# CPLD.net
KiCad netlist of a schematic drawn in Altium Designer
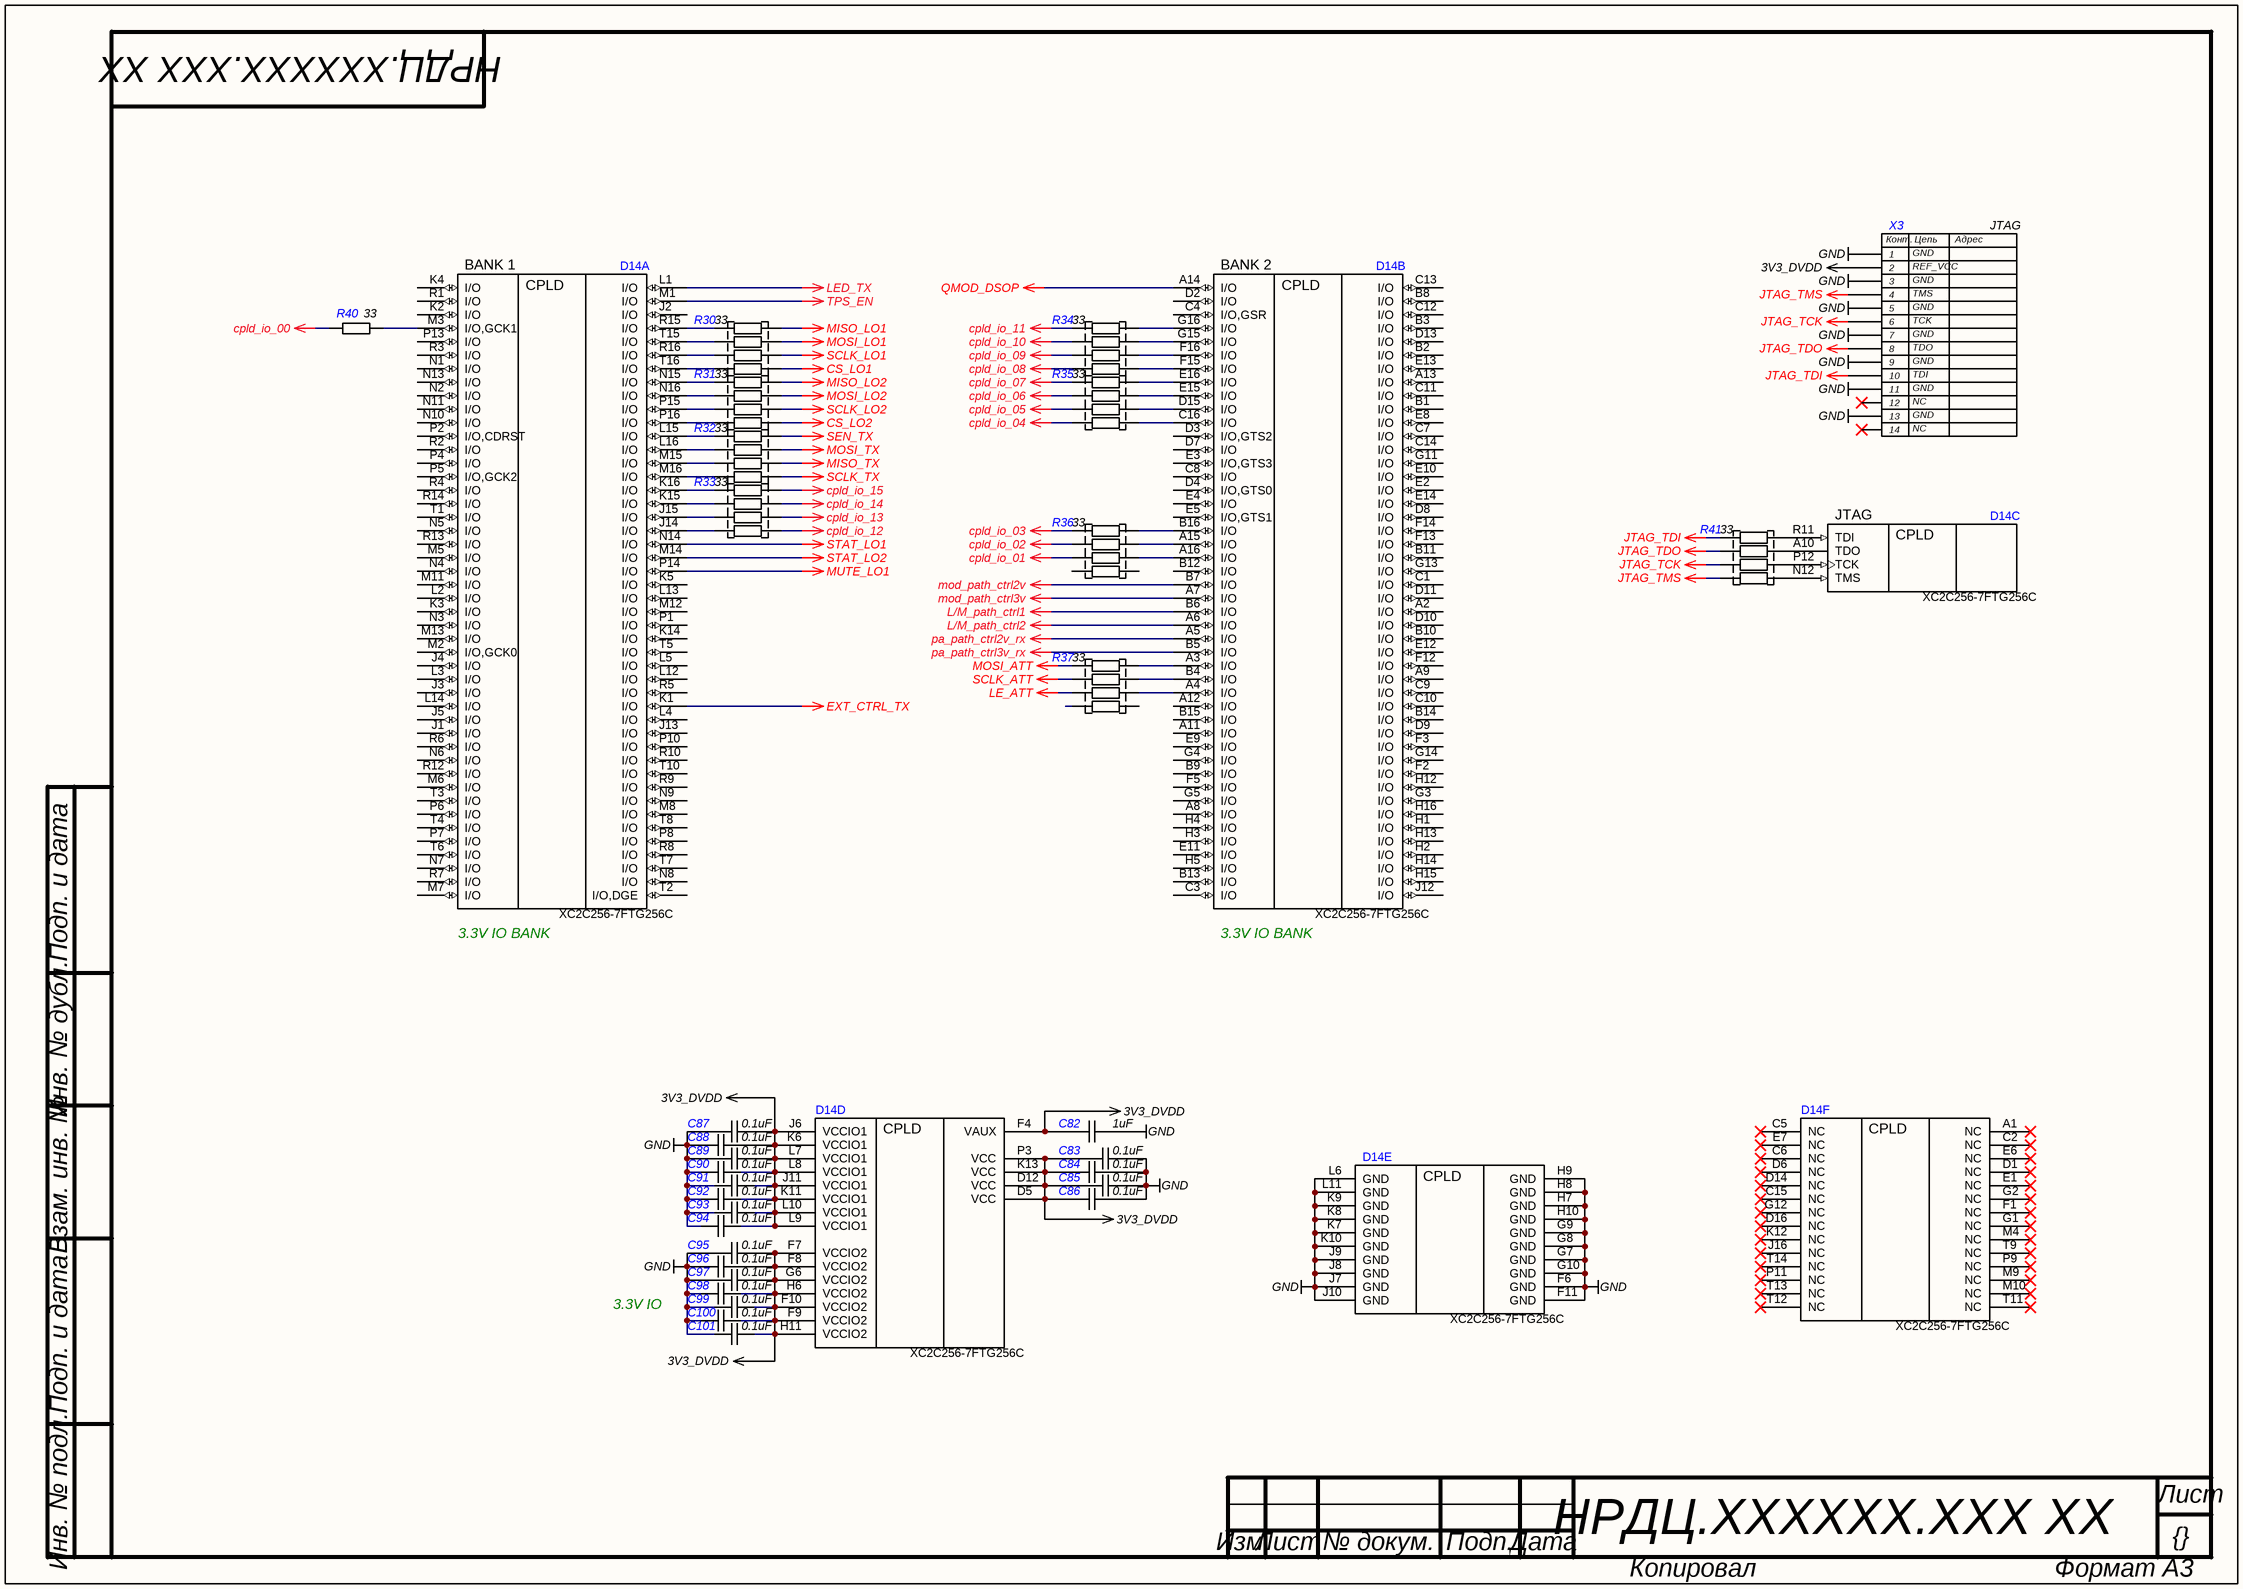
[diagram p0: CPLD.SchDoc]

(export (version "E")
  (design (tool "Eeschema 10.0.6"))
  (components
    (comp (ref "C82")
      (value "1uF")
      (footprint "C0402")
      (description "SMD Capacitor")
      (fields (field (name "MANUFACTURER") "Murata") (field (name "TOLERANCE") "10%"))
      (libsource (lib "Kintex_SDR") (part "CAP"))
    )
    (comp (ref "C83")
      (value "0.1uF")
      (footprint "C0402")
      (description "SMD Capacitor")
      (fields (field (name "MANUFACTURER") "Murata") (field (name "TOLERANCE") "10%"))
      (libsource (lib "Kintex_SDR") (part "CAP"))
    )
    (comp (ref "C84")
      (value "0.1uF")
      (footprint "C0402")
      (description "SMD Capacitor")
      (fields (field (name "MANUFACTURER") "Murata") (field (name "TOLERANCE") "10%"))
      (libsource (lib "Kintex_SDR") (part "CAP"))
    )
    (comp (ref "C85")
      (value "0.1uF")
      (footprint "C0402")
      (description "SMD Capacitor")
      (fields (field (name "MANUFACTURER") "Murata") (field (name "TOLERANCE") "10%"))
      (libsource (lib "Kintex_SDR") (part "CAP"))
    )
    (comp (ref "C86")
      (value "0.1uF")
      (footprint "C0402")
      (description "SMD Capacitor")
      (fields (field (name "MANUFACTURER") "Murata") (field (name "TOLERANCE") "10%"))
      (libsource (lib "Kintex_SDR") (part "CAP"))
    )
    (comp (ref "C87")
      (value "0.1uF")
      (footprint "C0402")
      (description "SMD Capacitor")
      (fields (field (name "MANUFACTURER") "Murata") (field (name "TOLERANCE") "10%"))
      (libsource (lib "Kintex_SDR") (part "CAP"))
    )
    (comp (ref "C88")
      (value "0.1uF")
      (footprint "C0402")
      (description "SMD Capacitor")
      (fields (field (name "MANUFACTURER") "Murata") (field (name "TOLERANCE") "10%"))
      (libsource (lib "Kintex_SDR") (part "CAP"))
    )
    (comp (ref "C89")
      (value "0.1uF")
      (footprint "C0402")
      (description "SMD Capacitor")
      (fields (field (name "MANUFACTURER") "Murata") (field (name "TOLERANCE") "10%"))
      (libsource (lib "Kintex_SDR") (part "CAP"))
    )
    (comp (ref "C90")
      (value "0.1uF")
      (footprint "C0402")
      (description "SMD Capacitor")
      (fields (field (name "MANUFACTURER") "Murata") (field (name "TOLERANCE") "10%"))
      (libsource (lib "Kintex_SDR") (part "CAP"))
    )
    (comp (ref "C91")
      (value "0.1uF")
      (footprint "C0402")
      (description "SMD Capacitor")
      (fields (field (name "MANUFACTURER") "Murata") (field (name "TOLERANCE") "10%"))
      (libsource (lib "Kintex_SDR") (part "CAP"))
    )
    (comp (ref "C92")
      (value "0.1uF")
      (footprint "C0402")
      (description "SMD Capacitor")
      (fields (field (name "MANUFACTURER") "Murata") (field (name "TOLERANCE") "10%"))
      (libsource (lib "Kintex_SDR") (part "CAP"))
    )
    (comp (ref "C93")
      (value "0.1uF")
      (footprint "C0402")
      (description "SMD Capacitor")
      (fields (field (name "MANUFACTURER") "Murata") (field (name "TOLERANCE") "10%"))
      (libsource (lib "Kintex_SDR") (part "CAP"))
    )
    (comp (ref "C94")
      (value "0.1uF")
      (footprint "C0402")
      (description "SMD Capacitor")
      (fields (field (name "MANUFACTURER") "Murata") (field (name "TOLERANCE") "10%"))
      (libsource (lib "Kintex_SDR") (part "CAP"))
    )
    (comp (ref "C95")
      (value "0.1uF")
      (footprint "C0402")
      (description "SMD Capacitor")
      (fields (field (name "MANUFACTURER") "Murata") (field (name "TOLERANCE") "10%"))
      (libsource (lib "Kintex_SDR") (part "CAP"))
    )
    (comp (ref "C96")
      (value "0.1uF")
      (footprint "C0402")
      (description "SMD Capacitor")
      (fields (field (name "MANUFACTURER") "Murata") (field (name "TOLERANCE") "10%"))
      (libsource (lib "Kintex_SDR") (part "CAP"))
    )
    (comp (ref "C97")
      (value "0.1uF")
      (footprint "C0402")
      (description "SMD Capacitor")
      (fields (field (name "MANUFACTURER") "Murata") (field (name "TOLERANCE") "10%"))
      (libsource (lib "Kintex_SDR") (part "CAP"))
    )
    (comp (ref "C98")
      (value "0.1uF")
      (footprint "C0402")
      (description "SMD Capacitor")
      (fields (field (name "MANUFACTURER") "Murata") (field (name "TOLERANCE") "10%"))
      (libsource (lib "Kintex_SDR") (part "CAP"))
    )
    (comp (ref "C99")
      (value "0.1uF")
      (footprint "C0402")
      (description "SMD Capacitor")
      (fields (field (name "MANUFACTURER") "Murata") (field (name "TOLERANCE") "10%"))
      (libsource (lib "Kintex_SDR") (part "CAP"))
    )
    (comp (ref "C100")
      (value "0.1uF")
      (footprint "C0402")
      (description "SMD Capacitor")
      (fields (field (name "MANUFACTURER") "Murata") (field (name "TOLERANCE") "10%"))
      (libsource (lib "Kintex_SDR") (part "CAP"))
    )
    (comp (ref "C101")
      (value "0.1uF")
      (footprint "C0402")
      (description "SMD Capacitor")
      (fields (field (name "MANUFACTURER") "Murata") (field (name "TOLERANCE") "10%"))
      (libsource (lib "Kintex_SDR") (part "CAP"))
    )
    (comp (ref "D14")
      (value "XC2C256-7FTG256C")
      (footprint "DBLib:FTG256")
      (description "CoolRunner-II 1.8V, 256 Macrocell CPLD, 184 User I/Os, 256-Ball FTBGA, Commercial Grade, Pb-Free")
      (libsource (lib "DBLib") (part "XC2C256-7FTG256C"))
    )
    (comp (ref "R30")
      (value "33")
      (footprint "EXN8V")
      (description "Chip Resistor Array")
      (fields (field (name "TOLERANCE") "5%") (field (name "MANUFACTURER") "Panasonic"))
      (libsource (lib "") (part "RES 4x0402_1"))
    )
    (comp (ref "R31")
      (value "33")
      (footprint "EXN8V")
      (description "Chip Resistor Array")
      (fields (field (name "TOLERANCE") "5%") (field (name "MANUFACTURER") "Panasonic"))
      (libsource (lib "") (part "RES 4x0402_2"))
    )
    (comp (ref "R32")
      (value "33")
      (footprint "EXN8V")
      (description "Chip Resistor Array")
      (fields (field (name "TOLERANCE") "5%") (field (name "MANUFACTURER") "Panasonic"))
      (libsource (lib "") (part "RES 4x0402_2"))
    )
    (comp (ref "R33")
      (value "33")
      (footprint "EXN8V")
      (description "Chip Resistor Array")
      (fields (field (name "TOLERANCE") "5%") (field (name "MANUFACTURER") "Panasonic"))
      (libsource (lib "Kintex_SDR") (part "RES 4x0402"))
    )
    (comp (ref "R34")
      (value "33")
      (footprint "EXN8V")
      (description "Chip Resistor Array")
      (fields (field (name "TOLERANCE") "5%") (field (name "MANUFACTURER") "Panasonic"))
      (libsource (lib "") (part "RES 4x0402_3"))
    )
    (comp (ref "R35")
      (value "33")
      (footprint "EXN8V")
      (description "Chip Resistor Array")
      (fields (field (name "TOLERANCE") "5%") (field (name "MANUFACTURER") "Panasonic"))
      (libsource (lib "") (part "RES 4x0402_3"))
    )
    (comp (ref "R36")
      (value "33")
      (footprint "EXN8V")
      (description "Chip Resistor Array")
      (fields (field (name "TOLERANCE") "5%") (field (name "MANUFACTURER") "Panasonic"))
      (libsource (lib "") (part "RES 4x0402_3"))
    )
    (comp (ref "R37")
      (value "33")
      (footprint "EXN8V")
      (description "Chip Resistor Array")
      (fields (field (name "TOLERANCE") "5%") (field (name "MANUFACTURER") "Panasonic"))
      (libsource (lib "") (part "RES 4x0402_4"))
    )
    (comp (ref "R40")
      (value "33")
      (footprint "R0402")
      (description "SMD Resistor")
      (fields (field (name "POWER") "0.1 Wt") (field (name "TOLERANCE") "1%"))
      (libsource (lib "Kintex_SDR") (part "RES"))
    )
    (comp (ref "R41")
      (value "33")
      (footprint "EXN8V")
      (description "Chip Resistor Array")
      (fields (field (name "TOLERANCE") "5%") (field (name "MANUFACTURER") "Panasonic"))
      (libsource (lib "") (part "RES 4x0402_4"))
    )
    (comp (ref "X3")
      (value "JTAG")
      (footprint "DBLib:JTAG Mail 2mm")
      (description "2.00mm Pitch, Milli-Grid PCB Header, Dual Row, Vertical, Through Hole, Shrouded, 14\r\nCircuits")
      (fields (field (name "MANUFACTURER") "Molex"))
      (libsource (lib "DBLib") (part "HDR Debug_14-pin"))
    )
  )
  (nets
    (net (code "1") (name "3V3_DVDD") (class "Default")
      (node (ref "C100") (pin "2") (pinfunction "2_2") (pintype "passive"))
      (node (ref "C101") (pin "2") (pinfunction "2_2") (pintype "passive"))
      (node (ref "C82") (pin "1") (pinfunction "1_1") (pintype "passive"))
      (node (ref "C83") (pin "1") (pinfunction "1_1") (pintype "passive"))
      (node (ref "C84") (pin "1") (pinfunction "1_1") (pintype "passive"))
      (node (ref "C85") (pin "1") (pinfunction "1_1") (pintype "passive"))
      (node (ref "C86") (pin "1") (pinfunction "1_1") (pintype "passive"))
      (node (ref "C87") (pin "2") (pinfunction "2_2") (pintype "passive"))
      (node (ref "C88") (pin "2") (pinfunction "2_2") (pintype "passive"))
      (node (ref "C89") (pin "2") (pinfunction "2_2") (pintype "passive"))
      (node (ref "C90") (pin "2") (pinfunction "2_2") (pintype "passive"))
      (node (ref "C91") (pin "2") (pinfunction "2_2") (pintype "passive"))
      (node (ref "C92") (pin "2") (pinfunction "2_2") (pintype "passive"))
      (node (ref "C93") (pin "2") (pinfunction "2_2") (pintype "passive"))
      (node (ref "C94") (pin "2") (pinfunction "2_2") (pintype "passive"))
      (node (ref "C95") (pin "2") (pinfunction "2_2") (pintype "passive"))
      (node (ref "C96") (pin "2") (pinfunction "2_2") (pintype "passive"))
      (node (ref "C97") (pin "2") (pinfunction "2_2") (pintype "passive"))
      (node (ref "C98") (pin "2") (pinfunction "2_2") (pintype "passive"))
      (node (ref "C99") (pin "2") (pinfunction "2_2") (pintype "passive"))
      (node (ref "D14") (pin "D12") (pinfunction "VCC_D12") (pintype "power_in"))
      (node (ref "D14") (pin "D5") (pinfunction "VCC_D5") (pintype "power_in"))
      (node (ref "D14") (pin "F10") (pinfunction "VCCIO2_F10") (pintype "power_in"))
      (node (ref "D14") (pin "F4") (pinfunction "VAUX_F4") (pintype "power_in"))
      (node (ref "D14") (pin "F7") (pinfunction "VCCIO2_F7") (pintype "power_in"))
      (node (ref "D14") (pin "F8") (pinfunction "VCCIO2_F8") (pintype "power_in"))
      (node (ref "D14") (pin "F9") (pinfunction "VCCIO2_F9") (pintype "power_in"))
      (node (ref "D14") (pin "G6") (pinfunction "VCCIO2_G6") (pintype "power_in"))
      (node (ref "D14") (pin "H11") (pinfunction "VCCIO2_H11") (pintype "power_in"))
      (node (ref "D14") (pin "H6") (pinfunction "VCCIO2_H6") (pintype "power_in"))
      (node (ref "D14") (pin "J11") (pinfunction "VCCIO1_J11") (pintype "power_in"))
      (node (ref "D14") (pin "J6") (pinfunction "VCCIO1_J6") (pintype "power_in"))
      (node (ref "D14") (pin "K11") (pinfunction "VCCIO1_K11") (pintype "power_in"))
      (node (ref "D14") (pin "K13") (pinfunction "VCC_K13") (pintype "power_in"))
      (node (ref "D14") (pin "K6") (pinfunction "VCCIO1_K6") (pintype "power_in"))
      (node (ref "D14") (pin "L10") (pinfunction "VCCIO1_L10") (pintype "power_in"))
      (node (ref "D14") (pin "L7") (pinfunction "VCCIO1_L7") (pintype "power_in"))
      (node (ref "D14") (pin "L8") (pinfunction "VCCIO1_L8") (pintype "power_in"))
      (node (ref "D14") (pin "L9") (pinfunction "VCCIO1_L9") (pintype "power_in"))
      (node (ref "D14") (pin "P3") (pinfunction "VCC_P3") (pintype "power_in"))
      (node (ref "X3") (pin "2") (pinfunction "2_2") (pintype "passive"))
    )
    (net (code "2") (name "CS_LO1") (class "Default")
      (node (ref "R30") (pin "5") (pinfunction "5_5") (pintype "passive"))
    )
    (net (code "3") (name "CS_LO2") (class "Default")
      (node (ref "R31") (pin "5") (pinfunction "5_5") (pintype "passive"))
    )
    (net (code "4") (name "EXT_CTRL_TX") (class "Default")
      (node (ref "D14") (pin "K1") (pinfunction "I/O_K1") (pintype "bidirectional"))
    )
    (net (code "5") (name "GND") (class "Default")
      (node (ref "C100") (pin "1") (pinfunction "1_1") (pintype "passive"))
      (node (ref "C101") (pin "1") (pinfunction "1_1") (pintype "passive"))
      (node (ref "C82") (pin "2") (pinfunction "2_2") (pintype "passive"))
      (node (ref "C83") (pin "2") (pinfunction "2_2") (pintype "passive"))
      (node (ref "C84") (pin "2") (pinfunction "2_2") (pintype "passive"))
      (node (ref "C85") (pin "2") (pinfunction "2_2") (pintype "passive"))
      (node (ref "C86") (pin "2") (pinfunction "2_2") (pintype "passive"))
      (node (ref "C87") (pin "1") (pinfunction "1_1") (pintype "passive"))
      (node (ref "C88") (pin "1") (pinfunction "1_1") (pintype "passive"))
      (node (ref "C89") (pin "1") (pinfunction "1_1") (pintype "passive"))
      (node (ref "C90") (pin "1") (pinfunction "1_1") (pintype "passive"))
      (node (ref "C91") (pin "1") (pinfunction "1_1") (pintype "passive"))
      (node (ref "C92") (pin "1") (pinfunction "1_1") (pintype "passive"))
      (node (ref "C93") (pin "1") (pinfunction "1_1") (pintype "passive"))
      (node (ref "C94") (pin "1") (pinfunction "1_1") (pintype "passive"))
      (node (ref "C95") (pin "1") (pinfunction "1_1") (pintype "passive"))
      (node (ref "C96") (pin "1") (pinfunction "1_1") (pintype "passive"))
      (node (ref "C97") (pin "1") (pinfunction "1_1") (pintype "passive"))
      (node (ref "C98") (pin "1") (pinfunction "1_1") (pintype "passive"))
      (node (ref "C99") (pin "1") (pinfunction "1_1") (pintype "passive"))
      (node (ref "D14") (pin "F11") (pinfunction "GND_F11") (pintype "power_in"))
      (node (ref "D14") (pin "F6") (pinfunction "GND_F6") (pintype "power_in"))
      (node (ref "D14") (pin "G10") (pinfunction "GND_G10") (pintype "power_in"))
      (node (ref "D14") (pin "G7") (pinfunction "GND_G7") (pintype "power_in"))
      (node (ref "D14") (pin "G8") (pinfunction "GND_G8") (pintype "power_in"))
      (node (ref "D14") (pin "G9") (pinfunction "GND_G9") (pintype "power_in"))
      (node (ref "D14") (pin "H10") (pinfunction "GND_H10") (pintype "power_in"))
      (node (ref "D14") (pin "H7") (pinfunction "GND_H7") (pintype "power_in"))
      (node (ref "D14") (pin "H8") (pinfunction "GND_H8") (pintype "power_in"))
      (node (ref "D14") (pin "H9") (pinfunction "GND_H9") (pintype "power_in"))
      (node (ref "D14") (pin "J10") (pinfunction "GND_J10") (pintype "power_in"))
      (node (ref "D14") (pin "J7") (pinfunction "GND_J7") (pintype "power_in"))
      (node (ref "D14") (pin "J8") (pinfunction "GND_J8") (pintype "power_in"))
      (node (ref "D14") (pin "J9") (pinfunction "GND_J9") (pintype "power_in"))
      (node (ref "D14") (pin "K10") (pinfunction "GND_K10") (pintype "power_in"))
      (node (ref "D14") (pin "K7") (pinfunction "GND_K7") (pintype "power_in"))
      (node (ref "D14") (pin "K8") (pinfunction "GND_K8") (pintype "power_in"))
      (node (ref "D14") (pin "K9") (pinfunction "GND_K9") (pintype "power_in"))
      (node (ref "D14") (pin "L11") (pinfunction "GND_L11") (pintype "power_in"))
      (node (ref "D14") (pin "L6") (pinfunction "GND_L6") (pintype "power_in"))
      (node (ref "X3") (pin "1") (pinfunction "1_1") (pintype "passive"))
      (node (ref "X3") (pin "11") (pinfunction "11_11") (pintype "passive"))
      (node (ref "X3") (pin "13") (pinfunction "13_13") (pintype "passive"))
      (node (ref "X3") (pin "3") (pinfunction "3_3") (pintype "passive"))
      (node (ref "X3") (pin "5") (pinfunction "5_5") (pintype "passive"))
      (node (ref "X3") (pin "7") (pinfunction "7_7") (pintype "passive"))
      (node (ref "X3") (pin "9") (pinfunction "9_9") (pintype "passive"))
    )
    (net (code "6") (name "JTAG_TCK") (class "Default")
      (node (ref "R41") (pin "6") (pinfunction "6_6") (pintype "passive"))
      (node (ref "X3") (pin "6") (pinfunction "6_6") (pintype "passive"))
    )
    (net (code "7") (name "JTAG_TDI") (class "Default")
      (node (ref "R41") (pin "8") (pinfunction "8_8") (pintype "passive"))
      (node (ref "X3") (pin "10") (pinfunction "10_10") (pintype "passive"))
    )
    (net (code "8") (name "JTAG_TDO") (class "Default")
      (node (ref "R41") (pin "7") (pinfunction "7_7") (pintype "passive"))
      (node (ref "X3") (pin "8") (pinfunction "8_8") (pintype "passive"))
    )
    (net (code "9") (name "JTAG_TMS") (class "Default")
      (node (ref "R41") (pin "5") (pinfunction "5_5") (pintype "passive"))
      (node (ref "X3") (pin "4") (pinfunction "4_4") (pintype "passive"))
    )
    (net (code "10") (name "LED_TX") (class "Default")
      (node (ref "D14") (pin "L1") (pinfunction "I/O_L1") (pintype "bidirectional"))
    )
    (net (code "11") (name "LE_ATT") (class "Default")
      (node (ref "R37") (pin "6") (pinfunction "6_6") (pintype "passive"))
    )
    (net (code "12") (name "L{slash}M_path_ctrl1") (class "Default")
      (node (ref "D14") (pin "B6") (pinfunction "I/O_B6") (pintype "bidirectional"))
    )
    (net (code "13") (name "L{slash}M_path_ctrl2") (class "Default")
      (node (ref "D14") (pin "A6") (pinfunction "I/O_A6") (pintype "bidirectional"))
    )
    (net (code "14") (name "MISO_LO1") (class "Default")
      (node (ref "R30") (pin "8") (pinfunction "8_8") (pintype "passive"))
    )
    (net (code "15") (name "MISO_LO2") (class "Default")
      (node (ref "R31") (pin "8") (pinfunction "8_8") (pintype "passive"))
    )
    (net (code "16") (name "MISO_TX") (class "Default")
      (node (ref "R32") (pin "6") (pinfunction "6_6") (pintype "passive"))
    )
    (net (code "17") (name "MOSI_ATT") (class "Default")
      (node (ref "R37") (pin "8") (pinfunction "8_8") (pintype "passive"))
    )
    (net (code "18") (name "MOSI_LO1") (class "Default")
      (node (ref "R30") (pin "7") (pinfunction "7_7") (pintype "passive"))
    )
    (net (code "19") (name "MOSI_LO2") (class "Default")
      (node (ref "R31") (pin "7") (pinfunction "7_7") (pintype "passive"))
    )
    (net (code "20") (name "MOSI_TX") (class "Default")
      (node (ref "R32") (pin "7") (pinfunction "7_7") (pintype "passive"))
    )
    (net (code "21") (name "MUTE_LO1") (class "Default")
      (node (ref "D14") (pin "P14") (pinfunction "I/O_P14") (pintype "bidirectional"))
    )
    (net (code "22") (name "Net-(D14A-I{slash}O,GCK1)") (class "Default")
      (node (ref "D14") (pin "M3") (pinfunction "I/O,GCK1_M3") (pintype "bidirectional"))
      (node (ref "R40") (pin "1") (pinfunction "1_1") (pintype "passive"))
    )
    (net (code "23") (name "Net-(D14A-I{slash}O-PadJ14)") (class "Default")
      (node (ref "D14") (pin "J14") (pinfunction "I/O_J14") (pintype "bidirectional"))
      (node (ref "R33") (pin "1") (pinfunction "1_1") (pintype "passive"))
    )
    (net (code "24") (name "Net-(D14A-I{slash}O-PadJ15)") (class "Default")
      (node (ref "D14") (pin "J15") (pinfunction "I/O_J15") (pintype "bidirectional"))
      (node (ref "R33") (pin "2") (pinfunction "2_2") (pintype "passive"))
    )
    (net (code "25") (name "Net-(D14A-I{slash}O-PadK15)") (class "Default")
      (node (ref "D14") (pin "K15") (pinfunction "I/O_K15") (pintype "bidirectional"))
      (node (ref "R33") (pin "3") (pinfunction "3_3") (pintype "passive"))
    )
    (net (code "26") (name "Net-(D14A-I{slash}O-PadK16)") (class "Default")
      (node (ref "D14") (pin "K16") (pinfunction "I/O_K16") (pintype "bidirectional"))
      (node (ref "R33") (pin "4") (pinfunction "4_4") (pintype "passive"))
    )
    (net (code "27") (name "Net-(D14A-I{slash}O-PadL15)") (class "Default")
      (node (ref "D14") (pin "L15") (pinfunction "I/O_L15") (pintype "bidirectional"))
      (node (ref "R32") (pin "1") (pinfunction "1_1") (pintype "passive"))
    )
    (net (code "28") (name "Net-(D14A-I{slash}O-PadL16)") (class "Default")
      (node (ref "D14") (pin "L16") (pinfunction "I/O_L16") (pintype "bidirectional"))
      (node (ref "R32") (pin "2") (pinfunction "2_2") (pintype "passive"))
    )
    (net (code "29") (name "Net-(D14A-I{slash}O-PadM15)") (class "Default")
      (node (ref "D14") (pin "M15") (pinfunction "I/O_M15") (pintype "bidirectional"))
      (node (ref "R32") (pin "3") (pinfunction "3_3") (pintype "passive"))
    )
    (net (code "30") (name "Net-(D14A-I{slash}O-PadM16)") (class "Default")
      (node (ref "D14") (pin "M16") (pinfunction "I/O_M16") (pintype "bidirectional"))
      (node (ref "R32") (pin "4") (pinfunction "4_4") (pintype "passive"))
    )
    (net (code "31") (name "Net-(D14A-I{slash}O-PadN15)") (class "Default")
      (node (ref "D14") (pin "N15") (pinfunction "I/O_N15") (pintype "bidirectional"))
      (node (ref "R31") (pin "1") (pinfunction "1_1") (pintype "passive"))
    )
    (net (code "32") (name "Net-(D14A-I{slash}O-PadN16)") (class "Default")
      (node (ref "D14") (pin "N16") (pinfunction "I/O_N16") (pintype "bidirectional"))
      (node (ref "R31") (pin "2") (pinfunction "2_2") (pintype "passive"))
    )
    (net (code "33") (name "Net-(D14A-I{slash}O-PadP15)") (class "Default")
      (node (ref "D14") (pin "P15") (pinfunction "I/O_P15") (pintype "bidirectional"))
      (node (ref "R31") (pin "3") (pinfunction "3_3") (pintype "passive"))
    )
    (net (code "34") (name "Net-(D14A-I{slash}O-PadP16)") (class "Default")
      (node (ref "D14") (pin "P16") (pinfunction "I/O_P16") (pintype "bidirectional"))
      (node (ref "R31") (pin "4") (pinfunction "4_4") (pintype "passive"))
    )
    (net (code "35") (name "Net-(D14A-I{slash}O-PadR15)") (class "Default")
      (node (ref "D14") (pin "R15") (pinfunction "I/O_R15") (pintype "bidirectional"))
      (node (ref "R30") (pin "1") (pinfunction "1_1") (pintype "passive"))
    )
    (net (code "36") (name "Net-(D14A-I{slash}O-PadR16)") (class "Default")
      (node (ref "D14") (pin "R16") (pinfunction "I/O_R16") (pintype "bidirectional"))
      (node (ref "R30") (pin "2") (pinfunction "2_2") (pintype "passive"))
    )
    (net (code "37") (name "Net-(D14A-I{slash}O-PadT15)") (class "Default")
      (node (ref "D14") (pin "T15") (pinfunction "I/O_T15") (pintype "bidirectional"))
      (node (ref "R30") (pin "3") (pinfunction "3_3") (pintype "passive"))
    )
    (net (code "38") (name "Net-(D14A-I{slash}O-PadT16)") (class "Default")
      (node (ref "D14") (pin "T16") (pinfunction "I/O_T16") (pintype "bidirectional"))
      (node (ref "R30") (pin "4") (pinfunction "4_4") (pintype "passive"))
    )
    (net (code "39") (name "Net-(D14B-I{slash}O-PadA3)") (class "Default")
      (node (ref "D14") (pin "A3") (pinfunction "I/O_A3") (pintype "bidirectional"))
      (node (ref "R37") (pin "1") (pinfunction "1_1") (pintype "passive"))
    )
    (net (code "40") (name "Net-(D14B-I{slash}O-PadA4)") (class "Default")
      (node (ref "D14") (pin "A4") (pinfunction "I/O_A4") (pintype "bidirectional"))
      (node (ref "R37") (pin "3") (pinfunction "3_3") (pintype "passive"))
    )
    (net (code "41") (name "Net-(D14B-I{slash}O-PadA15)") (class "Default")
      (node (ref "D14") (pin "A15") (pinfunction "I/O_A15") (pintype "bidirectional"))
      (node (ref "R36") (pin "3") (pinfunction "3_3") (pintype "passive"))
    )
    (net (code "42") (name "Net-(D14B-I{slash}O-PadA16)") (class "Default")
      (node (ref "D14") (pin "A16") (pinfunction "I/O_A16") (pintype "bidirectional"))
      (node (ref "R36") (pin "2") (pinfunction "2_2") (pintype "passive"))
    )
    (net (code "43") (name "Net-(D14B-I{slash}O-PadB4)") (class "Default")
      (node (ref "D14") (pin "B4") (pinfunction "I/O_B4") (pintype "bidirectional"))
      (node (ref "R37") (pin "2") (pinfunction "2_2") (pintype "passive"))
    )
    (net (code "44") (name "Net-(D14B-I{slash}O-PadB16)") (class "Default")
      (node (ref "D14") (pin "B16") (pinfunction "I/O_B16") (pintype "bidirectional"))
      (node (ref "R36") (pin "4") (pinfunction "4_4") (pintype "passive"))
    )
    (net (code "45") (name "Net-(D14B-I{slash}O-PadC16)") (class "Default")
      (node (ref "D14") (pin "C16") (pinfunction "I/O_C16") (pintype "bidirectional"))
      (node (ref "R35") (pin "1") (pinfunction "1_1") (pintype "passive"))
    )
    (net (code "46") (name "Net-(D14B-I{slash}O-PadD15)") (class "Default")
      (node (ref "D14") (pin "D15") (pinfunction "I/O_D15") (pintype "bidirectional"))
      (node (ref "R35") (pin "2") (pinfunction "2_2") (pintype "passive"))
    )
    (net (code "47") (name "Net-(D14B-I{slash}O-PadE15)") (class "Default")
      (node (ref "D14") (pin "E15") (pinfunction "I/O_E15") (pintype "bidirectional"))
      (node (ref "R35") (pin "3") (pinfunction "3_3") (pintype "passive"))
    )
    (net (code "48") (name "Net-(D14B-I{slash}O-PadE16)") (class "Default")
      (node (ref "D14") (pin "E16") (pinfunction "I/O_E16") (pintype "bidirectional"))
      (node (ref "R35") (pin "4") (pinfunction "4_4") (pintype "passive"))
    )
    (net (code "49") (name "Net-(D14B-I{slash}O-PadF15)") (class "Default")
      (node (ref "D14") (pin "F15") (pinfunction "I/O_F15") (pintype "bidirectional"))
      (node (ref "R34") (pin "1") (pinfunction "1_1") (pintype "passive"))
    )
    (net (code "50") (name "Net-(D14B-I{slash}O-PadF16)") (class "Default")
      (node (ref "D14") (pin "F16") (pinfunction "I/O_F16") (pintype "bidirectional"))
      (node (ref "R34") (pin "2") (pinfunction "2_2") (pintype "passive"))
    )
    (net (code "51") (name "Net-(D14B-I{slash}O-PadG15)") (class "Default")
      (node (ref "D14") (pin "G15") (pinfunction "I/O_G15") (pintype "bidirectional"))
      (node (ref "R34") (pin "3") (pinfunction "3_3") (pintype "passive"))
    )
    (net (code "52") (name "Net-(D14B-I{slash}O-PadG16)") (class "Default")
      (node (ref "D14") (pin "G16") (pinfunction "I/O_G16") (pintype "bidirectional"))
      (node (ref "R34") (pin "4") (pinfunction "4_4") (pintype "passive"))
    )
    (net (code "53") (name "Net-(D14C-TCK)") (class "Default")
      (node (ref "D14") (pin "P12") (pinfunction "TCK_P12") (pintype "input"))
      (node (ref "R41") (pin "3") (pinfunction "3_3") (pintype "passive"))
    )
    (net (code "54") (name "Net-(D14C-TDI)") (class "Default")
      (node (ref "D14") (pin "R11") (pinfunction "TDI_R11") (pintype "input"))
      (node (ref "R41") (pin "1") (pinfunction "1_1") (pintype "passive"))
    )
    (net (code "55") (name "Net-(D14C-TDO)") (class "Default")
      (node (ref "D14") (pin "A10") (pinfunction "TDO_A10") (pintype "passive"))
      (node (ref "R41") (pin "2") (pinfunction "2_2") (pintype "passive"))
    )
    (net (code "56") (name "Net-(D14C-TMS)") (class "Default")
      (node (ref "D14") (pin "N12") (pinfunction "TMS_N12") (pintype "input"))
      (node (ref "R41") (pin "4") (pinfunction "4_4") (pintype "passive"))
    )
    (net (code "57") (name "QMOD_DSOP") (class "Default")
      (node (ref "D14") (pin "A14") (pinfunction "I/O_A14") (pintype "bidirectional"))
    )
    (net (code "58") (name "SCLK_ATT") (class "Default")
      (node (ref "R37") (pin "7") (pinfunction "7_7") (pintype "passive"))
    )
    (net (code "59") (name "SCLK_LO1") (class "Default")
      (node (ref "R30") (pin "6") (pinfunction "6_6") (pintype "passive"))
    )
    (net (code "60") (name "SCLK_LO2") (class "Default")
      (node (ref "R31") (pin "6") (pinfunction "6_6") (pintype "passive"))
    )
    (net (code "61") (name "SCLK_TX") (class "Default")
      (node (ref "R32") (pin "5") (pinfunction "5_5") (pintype "passive"))
    )
    (net (code "62") (name "SEN_TX") (class "Default")
      (node (ref "R32") (pin "8") (pinfunction "8_8") (pintype "passive"))
    )
    (net (code "63") (name "STAT_LO1") (class "Default")
      (node (ref "D14") (pin "N14") (pinfunction "I/O_N14") (pintype "bidirectional"))
    )
    (net (code "64") (name "STAT_LO2") (class "Default")
      (node (ref "D14") (pin "M14") (pinfunction "I/O_M14") (pintype "bidirectional"))
    )
    (net (code "65") (name "TPS_EN") (class "Default")
      (node (ref "D14") (pin "M1") (pinfunction "I/O_M1") (pintype "bidirectional"))
    )
    (net (code "66") (name "cpld_io_00") (class "Default")
      (node (ref "R40") (pin "2") (pinfunction "2_2") (pintype "passive"))
    )
    (net (code "67") (name "cpld_io_01") (class "Default")
      (node (ref "R36") (pin "7") (pinfunction "7_7") (pintype "passive"))
    )
    (net (code "68") (name "cpld_io_02") (class "Default")
      (node (ref "R36") (pin "6") (pinfunction "6_6") (pintype "passive"))
    )
    (net (code "69") (name "cpld_io_03") (class "Default")
      (node (ref "R36") (pin "5") (pinfunction "5_5") (pintype "passive"))
    )
    (net (code "70") (name "cpld_io_04") (class "Default")
      (node (ref "R35") (pin "8") (pinfunction "8_8") (pintype "passive"))
    )
    (net (code "71") (name "cpld_io_05") (class "Default")
      (node (ref "R35") (pin "7") (pinfunction "7_7") (pintype "passive"))
    )
    (net (code "72") (name "cpld_io_06") (class "Default")
      (node (ref "R35") (pin "6") (pinfunction "6_6") (pintype "passive"))
    )
    (net (code "73") (name "cpld_io_07") (class "Default")
      (node (ref "R35") (pin "5") (pinfunction "5_5") (pintype "passive"))
    )
    (net (code "74") (name "cpld_io_08") (class "Default")
      (node (ref "R34") (pin "8") (pinfunction "8_8") (pintype "passive"))
    )
    (net (code "75") (name "cpld_io_09") (class "Default")
      (node (ref "R34") (pin "7") (pinfunction "7_7") (pintype "passive"))
    )
    (net (code "76") (name "cpld_io_10") (class "Default")
      (node (ref "R34") (pin "6") (pinfunction "6_6") (pintype "passive"))
    )
    (net (code "77") (name "cpld_io_11") (class "Default")
      (node (ref "R34") (pin "5") (pinfunction "5_5") (pintype "passive"))
    )
    (net (code "78") (name "cpld_io_12") (class "Default")
      (node (ref "R33") (pin "8") (pinfunction "8_8") (pintype "passive"))
    )
    (net (code "79") (name "cpld_io_13") (class "Default")
      (node (ref "R33") (pin "7") (pinfunction "7_7") (pintype "passive"))
    )
    (net (code "80") (name "cpld_io_14") (class "Default")
      (node (ref "R33") (pin "6") (pinfunction "6_6") (pintype "passive"))
    )
    (net (code "81") (name "cpld_io_15") (class "Default")
      (node (ref "R33") (pin "5") (pinfunction "5_5") (pintype "passive"))
    )
    (net (code "82") (name "mod_path_ctrl2v") (class "Default")
      (node (ref "D14") (pin "B7") (pinfunction "I/O_B7") (pintype "bidirectional"))
    )
    (net (code "83") (name "mod_path_ctrl3v") (class "Default")
      (node (ref "D14") (pin "A7") (pinfunction "I/O_A7") (pintype "bidirectional"))
    )
    (net (code "84") (name "pa_path_ctrl2v_rx") (class "Default")
      (node (ref "D14") (pin "A5") (pinfunction "I/O_A5") (pintype "bidirectional"))
    )
    (net (code "85") (name "pa_path_ctrl3v_rx") (class "Default")
      (node (ref "D14") (pin "B5") (pinfunction "I/O_B5") (pintype "bidirectional"))
    )
    (net (code "86") (name "unconnected-(D14A-I{slash}O,CDRST-PadP2)") (class "Default")
      (node (ref "D14") (pin "P2") (pinfunction "I/O,CDRST_P2") (pintype "bidirectional"))
    )
    (net (code "87") (name "unconnected-(D14A-I{slash}O,DGE-PadT2)") (class "Default")
      (node (ref "D14") (pin "T2") (pinfunction "I/O,DGE_T2") (pintype "bidirectional"))
    )
    (net (code "88") (name "unconnected-(D14A-I{slash}O,GCK0-PadM2)") (class "Default")
      (node (ref "D14") (pin "M2") (pinfunction "I/O,GCK0_M2") (pintype "bidirectional"))
    )
    (net (code "89") (name "unconnected-(D14A-I{slash}O,GCK2-PadP5)") (class "Default")
      (node (ref "D14") (pin "P5") (pinfunction "I/O,GCK2_P5") (pintype "bidirectional"))
    )
    (net (code "90") (name "unconnected-(D14A-I{slash}O-PadJ1)") (class "Default")
      (node (ref "D14") (pin "J1") (pinfunction "I/O_J1") (pintype "bidirectional"))
    )
    (net (code "91") (name "unconnected-(D14A-I{slash}O-PadJ2)") (class "Default")
      (node (ref "D14") (pin "J2") (pinfunction "I/O_J2") (pintype "bidirectional"))
    )
    (net (code "92") (name "unconnected-(D14A-I{slash}O-PadJ3)") (class "Default")
      (node (ref "D14") (pin "J3") (pinfunction "I/O_J3") (pintype "bidirectional"))
    )
    (net (code "93") (name "unconnected-(D14A-I{slash}O-PadJ4)") (class "Default")
      (node (ref "D14") (pin "J4") (pinfunction "I/O_J4") (pintype "bidirectional"))
    )
    (net (code "94") (name "unconnected-(D14A-I{slash}O-PadJ5)") (class "Default")
      (node (ref "D14") (pin "J5") (pinfunction "I/O_J5") (pintype "bidirectional"))
    )
    (net (code "95") (name "unconnected-(D14A-I{slash}O-PadJ13)") (class "Default")
      (node (ref "D14") (pin "J13") (pinfunction "I/O_J13") (pintype "bidirectional"))
    )
    (net (code "96") (name "unconnected-(D14A-I{slash}O-PadK2)") (class "Default")
      (node (ref "D14") (pin "K2") (pinfunction "I/O_K2") (pintype "bidirectional"))
    )
    (net (code "97") (name "unconnected-(D14A-I{slash}O-PadK3)") (class "Default")
      (node (ref "D14") (pin "K3") (pinfunction "I/O_K3") (pintype "bidirectional"))
    )
    (net (code "98") (name "unconnected-(D14A-I{slash}O-PadK4)") (class "Default")
      (node (ref "D14") (pin "K4") (pinfunction "I/O_K4") (pintype "bidirectional"))
    )
    (net (code "99") (name "unconnected-(D14A-I{slash}O-PadK5)") (class "Default")
      (node (ref "D14") (pin "K5") (pinfunction "I/O_K5") (pintype "bidirectional"))
    )
    (net (code "100") (name "unconnected-(D14A-I{slash}O-PadK14)") (class "Default")
      (node (ref "D14") (pin "K14") (pinfunction "I/O_K14") (pintype "bidirectional"))
    )
    (net (code "101") (name "unconnected-(D14A-I{slash}O-PadL2)") (class "Default")
      (node (ref "D14") (pin "L2") (pinfunction "I/O_L2") (pintype "bidirectional"))
    )
    (net (code "102") (name "unconnected-(D14A-I{slash}O-PadL3)") (class "Default")
      (node (ref "D14") (pin "L3") (pinfunction "I/O_L3") (pintype "bidirectional"))
    )
    (net (code "103") (name "unconnected-(D14A-I{slash}O-PadL4)") (class "Default")
      (node (ref "D14") (pin "L4") (pinfunction "I/O_L4") (pintype "bidirectional"))
    )
    (net (code "104") (name "unconnected-(D14A-I{slash}O-PadL5)") (class "Default")
      (node (ref "D14") (pin "L5") (pinfunction "I/O_L5") (pintype "bidirectional"))
    )
    (net (code "105") (name "unconnected-(D14A-I{slash}O-PadL12)") (class "Default")
      (node (ref "D14") (pin "L12") (pinfunction "I/O_L12") (pintype "bidirectional"))
    )
    (net (code "106") (name "unconnected-(D14A-I{slash}O-PadL13)") (class "Default")
      (node (ref "D14") (pin "L13") (pinfunction "I/O_L13") (pintype "bidirectional"))
    )
    (net (code "107") (name "unconnected-(D14A-I{slash}O-PadL14)") (class "Default")
      (node (ref "D14") (pin "L14") (pinfunction "I/O_L14") (pintype "bidirectional"))
    )
    (net (code "108") (name "unconnected-(D14A-I{slash}O-PadM5)") (class "Default")
      (node (ref "D14") (pin "M5") (pinfunction "I/O_M5") (pintype "bidirectional"))
    )
    (net (code "109") (name "unconnected-(D14A-I{slash}O-PadM6)") (class "Default")
      (node (ref "D14") (pin "M6") (pinfunction "I/O_M6") (pintype "bidirectional"))
    )
    (net (code "110") (name "unconnected-(D14A-I{slash}O-PadM7)") (class "Default")
      (node (ref "D14") (pin "M7") (pinfunction "I/O_M7") (pintype "bidirectional"))
    )
    (net (code "111") (name "unconnected-(D14A-I{slash}O-PadM8)") (class "Default")
      (node (ref "D14") (pin "M8") (pinfunction "I/O_M8") (pintype "bidirectional"))
    )
    (net (code "112") (name "unconnected-(D14A-I{slash}O-PadM11)") (class "Default")
      (node (ref "D14") (pin "M11") (pinfunction "I/O_M11") (pintype "bidirectional"))
    )
    (net (code "113") (name "unconnected-(D14A-I{slash}O-PadM12)") (class "Default")
      (node (ref "D14") (pin "M12") (pinfunction "I/O_M12") (pintype "bidirectional"))
    )
    (net (code "114") (name "unconnected-(D14A-I{slash}O-PadM13)") (class "Default")
      (node (ref "D14") (pin "M13") (pinfunction "I/O_M13") (pintype "bidirectional"))
    )
    (net (code "115") (name "unconnected-(D14A-I{slash}O-PadN1)") (class "Default")
      (node (ref "D14") (pin "N1") (pinfunction "I/O_N1") (pintype "bidirectional"))
    )
    (net (code "116") (name "unconnected-(D14A-I{slash}O-PadN2)") (class "Default")
      (node (ref "D14") (pin "N2") (pinfunction "I/O_N2") (pintype "bidirectional"))
    )
    (net (code "117") (name "unconnected-(D14A-I{slash}O-PadN3)") (class "Default")
      (node (ref "D14") (pin "N3") (pinfunction "I/O_N3") (pintype "bidirectional"))
    )
    (net (code "118") (name "unconnected-(D14A-I{slash}O-PadN4)") (class "Default")
      (node (ref "D14") (pin "N4") (pinfunction "I/O_N4") (pintype "bidirectional"))
    )
    (net (code "119") (name "unconnected-(D14A-I{slash}O-PadN5)") (class "Default")
      (node (ref "D14") (pin "N5") (pinfunction "I/O_N5") (pintype "bidirectional"))
    )
    (net (code "120") (name "unconnected-(D14A-I{slash}O-PadN6)") (class "Default")
      (node (ref "D14") (pin "N6") (pinfunction "I/O_N6") (pintype "bidirectional"))
    )
    (net (code "121") (name "unconnected-(D14A-I{slash}O-PadN7)") (class "Default")
      (node (ref "D14") (pin "N7") (pinfunction "I/O_N7") (pintype "bidirectional"))
    )
    (net (code "122") (name "unconnected-(D14A-I{slash}O-PadN8)") (class "Default")
      (node (ref "D14") (pin "N8") (pinfunction "I/O_N8") (pintype "bidirectional"))
    )
    (net (code "123") (name "unconnected-(D14A-I{slash}O-PadN9)") (class "Default")
      (node (ref "D14") (pin "N9") (pinfunction "I/O_N9") (pintype "bidirectional"))
    )
    (net (code "124") (name "unconnected-(D14A-I{slash}O-PadN10)") (class "Default")
      (node (ref "D14") (pin "N10") (pinfunction "I/O_N10") (pintype "bidirectional"))
    )
    (net (code "125") (name "unconnected-(D14A-I{slash}O-PadN11)") (class "Default")
      (node (ref "D14") (pin "N11") (pinfunction "I/O_N11") (pintype "bidirectional"))
    )
    (net (code "126") (name "unconnected-(D14A-I{slash}O-PadN13)") (class "Default")
      (node (ref "D14") (pin "N13") (pinfunction "I/O_N13") (pintype "bidirectional"))
    )
    (net (code "127") (name "unconnected-(D14A-I{slash}O-PadP1)") (class "Default")
      (node (ref "D14") (pin "P1") (pinfunction "I/O_P1") (pintype "bidirectional"))
    )
    (net (code "128") (name "unconnected-(D14A-I{slash}O-PadP4)") (class "Default")
      (node (ref "D14") (pin "P4") (pinfunction "I/O_P4") (pintype "bidirectional"))
    )
    (net (code "129") (name "unconnected-(D14A-I{slash}O-PadP6)") (class "Default")
      (node (ref "D14") (pin "P6") (pinfunction "I/O_P6") (pintype "bidirectional"))
    )
    (net (code "130") (name "unconnected-(D14A-I{slash}O-PadP7)") (class "Default")
      (node (ref "D14") (pin "P7") (pinfunction "I/O_P7") (pintype "bidirectional"))
    )
    (net (code "131") (name "unconnected-(D14A-I{slash}O-PadP8)") (class "Default")
      (node (ref "D14") (pin "P8") (pinfunction "I/O_P8") (pintype "bidirectional"))
    )
    (net (code "132") (name "unconnected-(D14A-I{slash}O-PadP10)") (class "Default")
      (node (ref "D14") (pin "P10") (pinfunction "I/O_P10") (pintype "bidirectional"))
    )
    (net (code "133") (name "unconnected-(D14A-I{slash}O-PadP13)") (class "Default")
      (node (ref "D14") (pin "P13") (pinfunction "I/O_P13") (pintype "bidirectional"))
    )
    (net (code "134") (name "unconnected-(D14A-I{slash}O-PadR1)") (class "Default")
      (node (ref "D14") (pin "R1") (pinfunction "I/O_R1") (pintype "bidirectional"))
    )
    (net (code "135") (name "unconnected-(D14A-I{slash}O-PadR2)") (class "Default")
      (node (ref "D14") (pin "R2") (pinfunction "I/O_R2") (pintype "bidirectional"))
    )
    (net (code "136") (name "unconnected-(D14A-I{slash}O-PadR3)") (class "Default")
      (node (ref "D14") (pin "R3") (pinfunction "I/O_R3") (pintype "bidirectional"))
    )
    (net (code "137") (name "unconnected-(D14A-I{slash}O-PadR4)") (class "Default")
      (node (ref "D14") (pin "R4") (pinfunction "I/O_R4") (pintype "bidirectional"))
    )
    (net (code "138") (name "unconnected-(D14A-I{slash}O-PadR5)") (class "Default")
      (node (ref "D14") (pin "R5") (pinfunction "I/O_R5") (pintype "bidirectional"))
    )
    (net (code "139") (name "unconnected-(D14A-I{slash}O-PadR6)") (class "Default")
      (node (ref "D14") (pin "R6") (pinfunction "I/O_R6") (pintype "bidirectional"))
    )
    (net (code "140") (name "unconnected-(D14A-I{slash}O-PadR7)") (class "Default")
      (node (ref "D14") (pin "R7") (pinfunction "I/O_R7") (pintype "bidirectional"))
    )
    (net (code "141") (name "unconnected-(D14A-I{slash}O-PadR8)") (class "Default")
      (node (ref "D14") (pin "R8") (pinfunction "I/O_R8") (pintype "bidirectional"))
    )
    (net (code "142") (name "unconnected-(D14A-I{slash}O-PadR9)") (class "Default")
      (node (ref "D14") (pin "R9") (pinfunction "I/O_R9") (pintype "bidirectional"))
    )
    (net (code "143") (name "unconnected-(D14A-I{slash}O-PadR10)") (class "Default")
      (node (ref "D14") (pin "R10") (pinfunction "I/O_R10") (pintype "bidirectional"))
    )
    (net (code "144") (name "unconnected-(D14A-I{slash}O-PadR12)") (class "Default")
      (node (ref "D14") (pin "R12") (pinfunction "I/O_R12") (pintype "bidirectional"))
    )
    (net (code "145") (name "unconnected-(D14A-I{slash}O-PadR13)") (class "Default")
      (node (ref "D14") (pin "R13") (pinfunction "I/O_R13") (pintype "bidirectional"))
    )
    (net (code "146") (name "unconnected-(D14A-I{slash}O-PadR14)") (class "Default")
      (node (ref "D14") (pin "R14") (pinfunction "I/O_R14") (pintype "bidirectional"))
    )
    (net (code "147") (name "unconnected-(D14A-I{slash}O-PadT1)") (class "Default")
      (node (ref "D14") (pin "T1") (pinfunction "I/O_T1") (pintype "bidirectional"))
    )
    (net (code "148") (name "unconnected-(D14A-I{slash}O-PadT3)") (class "Default")
      (node (ref "D14") (pin "T3") (pinfunction "I/O_T3") (pintype "bidirectional"))
    )
    (net (code "149") (name "unconnected-(D14A-I{slash}O-PadT4)") (class "Default")
      (node (ref "D14") (pin "T4") (pinfunction "I/O_T4") (pintype "bidirectional"))
    )
    (net (code "150") (name "unconnected-(D14A-I{slash}O-PadT5)") (class "Default")
      (node (ref "D14") (pin "T5") (pinfunction "I/O_T5") (pintype "bidirectional"))
    )
    (net (code "151") (name "unconnected-(D14A-I{slash}O-PadT6)") (class "Default")
      (node (ref "D14") (pin "T6") (pinfunction "I/O_T6") (pintype "bidirectional"))
    )
    (net (code "152") (name "unconnected-(D14A-I{slash}O-PadT7)") (class "Default")
      (node (ref "D14") (pin "T7") (pinfunction "I/O_T7") (pintype "bidirectional"))
    )
    (net (code "153") (name "unconnected-(D14A-I{slash}O-PadT8)") (class "Default")
      (node (ref "D14") (pin "T8") (pinfunction "I/O_T8") (pintype "bidirectional"))
    )
    (net (code "154") (name "unconnected-(D14A-I{slash}O-PadT10)") (class "Default")
      (node (ref "D14") (pin "T10") (pinfunction "I/O_T10") (pintype "bidirectional"))
    )
    (net (code "155") (name "unconnected-(D14B-I{slash}O,GSR-PadC4)") (class "Default")
      (node (ref "D14") (pin "C4") (pinfunction "I/O,GSR_C4") (pintype "bidirectional"))
    )
    (net (code "156") (name "unconnected-(D14B-I{slash}O,GTS0-PadD4)") (class "Default")
      (node (ref "D14") (pin "D4") (pinfunction "I/O,GTS0_D4") (pintype "bidirectional"))
    )
    (net (code "157") (name "unconnected-(D14B-I{slash}O,GTS1-PadE5)") (class "Default")
      (node (ref "D14") (pin "E5") (pinfunction "I/O,GTS1_E5") (pintype "bidirectional"))
    )
    (net (code "158") (name "unconnected-(D14B-I{slash}O,GTS2-PadD3)") (class "Default")
      (node (ref "D14") (pin "D3") (pinfunction "I/O,GTS2_D3") (pintype "bidirectional"))
    )
    (net (code "159") (name "unconnected-(D14B-I{slash}O,GTS3-PadE3)") (class "Default")
      (node (ref "D14") (pin "E3") (pinfunction "I/O,GTS3_E3") (pintype "bidirectional"))
    )
    (net (code "160") (name "unconnected-(D14B-I{slash}O-PadA2)") (class "Default")
      (node (ref "D14") (pin "A2") (pinfunction "I/O_A2") (pintype "bidirectional"))
    )
    (net (code "161") (name "unconnected-(D14B-I{slash}O-PadA8)") (class "Default")
      (node (ref "D14") (pin "A8") (pinfunction "I/O_A8") (pintype "bidirectional"))
    )
    (net (code "162") (name "unconnected-(D14B-I{slash}O-PadA9)") (class "Default")
      (node (ref "D14") (pin "A9") (pinfunction "I/O_A9") (pintype "bidirectional"))
    )
    (net (code "163") (name "unconnected-(D14B-I{slash}O-PadA11)") (class "Default")
      (node (ref "D14") (pin "A11") (pinfunction "I/O_A11") (pintype "bidirectional"))
    )
    (net (code "164") (name "unconnected-(D14B-I{slash}O-PadA12)") (class "Default")
      (node (ref "D14") (pin "A12") (pinfunction "I/O_A12") (pintype "bidirectional"))
    )
    (net (code "165") (name "unconnected-(D14B-I{slash}O-PadA13)") (class "Default")
      (node (ref "D14") (pin "A13") (pinfunction "I/O_A13") (pintype "bidirectional"))
    )
    (net (code "166") (name "unconnected-(D14B-I{slash}O-PadB1)") (class "Default")
      (node (ref "D14") (pin "B1") (pinfunction "I/O_B1") (pintype "bidirectional"))
    )
    (net (code "167") (name "unconnected-(D14B-I{slash}O-PadB2)") (class "Default")
      (node (ref "D14") (pin "B2") (pinfunction "I/O_B2") (pintype "bidirectional"))
    )
    (net (code "168") (name "unconnected-(D14B-I{slash}O-PadB3)") (class "Default")
      (node (ref "D14") (pin "B3") (pinfunction "I/O_B3") (pintype "bidirectional"))
    )
    (net (code "169") (name "unconnected-(D14B-I{slash}O-PadB8)") (class "Default")
      (node (ref "D14") (pin "B8") (pinfunction "I/O_B8") (pintype "bidirectional"))
    )
    (net (code "170") (name "unconnected-(D14B-I{slash}O-PadB9)") (class "Default")
      (node (ref "D14") (pin "B9") (pinfunction "I/O_B9") (pintype "bidirectional"))
    )
    (net (code "171") (name "unconnected-(D14B-I{slash}O-PadB10)") (class "Default")
      (node (ref "D14") (pin "B10") (pinfunction "I/O_B10") (pintype "bidirectional"))
    )
    (net (code "172") (name "unconnected-(D14B-I{slash}O-PadB11)") (class "Default")
      (node (ref "D14") (pin "B11") (pinfunction "I/O_B11") (pintype "bidirectional"))
    )
    (net (code "173") (name "unconnected-(D14B-I{slash}O-PadB12)") (class "Default")
      (node (ref "D14") (pin "B12") (pinfunction "I/O_B12") (pintype "bidirectional"))
    )
    (net (code "174") (name "unconnected-(D14B-I{slash}O-PadB13)") (class "Default")
      (node (ref "D14") (pin "B13") (pinfunction "I/O_B13") (pintype "bidirectional"))
    )
    (net (code "175") (name "unconnected-(D14B-I{slash}O-PadB14)") (class "Default")
      (node (ref "D14") (pin "B14") (pinfunction "I/O_B14") (pintype "bidirectional"))
    )
    (net (code "176") (name "unconnected-(D14B-I{slash}O-PadB15)") (class "Default")
      (node (ref "D14") (pin "B15") (pinfunction "I/O_B15") (pintype "bidirectional"))
    )
    (net (code "177") (name "unconnected-(D14B-I{slash}O-PadC1)") (class "Default")
      (node (ref "D14") (pin "C1") (pinfunction "I/O_C1") (pintype "bidirectional"))
    )
    (net (code "178") (name "unconnected-(D14B-I{slash}O-PadC3)") (class "Default")
      (node (ref "D14") (pin "C3") (pinfunction "I/O_C3") (pintype "bidirectional"))
    )
    (net (code "179") (name "unconnected-(D14B-I{slash}O-PadC7)") (class "Default")
      (node (ref "D14") (pin "C7") (pinfunction "I/O_C7") (pintype "bidirectional"))
    )
    (net (code "180") (name "unconnected-(D14B-I{slash}O-PadC8)") (class "Default")
      (node (ref "D14") (pin "C8") (pinfunction "I/O_C8") (pintype "bidirectional"))
    )
    (net (code "181") (name "unconnected-(D14B-I{slash}O-PadC9)") (class "Default")
      (node (ref "D14") (pin "C9") (pinfunction "I/O_C9") (pintype "bidirectional"))
    )
    (net (code "182") (name "unconnected-(D14B-I{slash}O-PadC10)") (class "Default")
      (node (ref "D14") (pin "C10") (pinfunction "I/O_C10") (pintype "bidirectional"))
    )
    (net (code "183") (name "unconnected-(D14B-I{slash}O-PadC11)") (class "Default")
      (node (ref "D14") (pin "C11") (pinfunction "I/O_C11") (pintype "bidirectional"))
    )
    (net (code "184") (name "unconnected-(D14B-I{slash}O-PadC12)") (class "Default")
      (node (ref "D14") (pin "C12") (pinfunction "I/O_C12") (pintype "bidirectional"))
    )
    (net (code "185") (name "unconnected-(D14B-I{slash}O-PadC13)") (class "Default")
      (node (ref "D14") (pin "C13") (pinfunction "I/O_C13") (pintype "bidirectional"))
    )
    (net (code "186") (name "unconnected-(D14B-I{slash}O-PadC14)") (class "Default")
      (node (ref "D14") (pin "C14") (pinfunction "I/O_C14") (pintype "bidirectional"))
    )
    (net (code "187") (name "unconnected-(D14B-I{slash}O-PadD2)") (class "Default")
      (node (ref "D14") (pin "D2") (pinfunction "I/O_D2") (pintype "bidirectional"))
    )
    (net (code "188") (name "unconnected-(D14B-I{slash}O-PadD7)") (class "Default")
      (node (ref "D14") (pin "D7") (pinfunction "I/O_D7") (pintype "bidirectional"))
    )
    (net (code "189") (name "unconnected-(D14B-I{slash}O-PadD8)") (class "Default")
      (node (ref "D14") (pin "D8") (pinfunction "I/O_D8") (pintype "bidirectional"))
    )
    (net (code "190") (name "unconnected-(D14B-I{slash}O-PadD9)") (class "Default")
      (node (ref "D14") (pin "D9") (pinfunction "I/O_D9") (pintype "bidirectional"))
    )
    (net (code "191") (name "unconnected-(D14B-I{slash}O-PadD10)") (class "Default")
      (node (ref "D14") (pin "D10") (pinfunction "I/O_D10") (pintype "bidirectional"))
    )
    (net (code "192") (name "unconnected-(D14B-I{slash}O-PadD11)") (class "Default")
      (node (ref "D14") (pin "D11") (pinfunction "I/O_D11") (pintype "bidirectional"))
    )
    (net (code "193") (name "unconnected-(D14B-I{slash}O-PadD13)") (class "Default")
      (node (ref "D14") (pin "D13") (pinfunction "I/O_D13") (pintype "bidirectional"))
    )
    (net (code "194") (name "unconnected-(D14B-I{slash}O-PadE2)") (class "Default")
      (node (ref "D14") (pin "E2") (pinfunction "I/O_E2") (pintype "bidirectional"))
    )
    (net (code "195") (name "unconnected-(D14B-I{slash}O-PadE4)") (class "Default")
      (node (ref "D14") (pin "E4") (pinfunction "I/O_E4") (pintype "bidirectional"))
    )
    (net (code "196") (name "unconnected-(D14B-I{slash}O-PadE8)") (class "Default")
      (node (ref "D14") (pin "E8") (pinfunction "I/O_E8") (pintype "bidirectional"))
    )
    (net (code "197") (name "unconnected-(D14B-I{slash}O-PadE9)") (class "Default")
      (node (ref "D14") (pin "E9") (pinfunction "I/O_E9") (pintype "bidirectional"))
    )
    (net (code "198") (name "unconnected-(D14B-I{slash}O-PadE10)") (class "Default")
      (node (ref "D14") (pin "E10") (pinfunction "I/O_E10") (pintype "bidirectional"))
    )
    (net (code "199") (name "unconnected-(D14B-I{slash}O-PadE11)") (class "Default")
      (node (ref "D14") (pin "E11") (pinfunction "I/O_E11") (pintype "bidirectional"))
    )
    (net (code "200") (name "unconnected-(D14B-I{slash}O-PadE12)") (class "Default")
      (node (ref "D14") (pin "E12") (pinfunction "I/O_E12") (pintype "bidirectional"))
    )
    (net (code "201") (name "unconnected-(D14B-I{slash}O-PadE13)") (class "Default")
      (node (ref "D14") (pin "E13") (pinfunction "I/O_E13") (pintype "bidirectional"))
    )
    (net (code "202") (name "unconnected-(D14B-I{slash}O-PadE14)") (class "Default")
      (node (ref "D14") (pin "E14") (pinfunction "I/O_E14") (pintype "bidirectional"))
    )
    (net (code "203") (name "unconnected-(D14B-I{slash}O-PadF2)") (class "Default")
      (node (ref "D14") (pin "F2") (pinfunction "I/O_F2") (pintype "bidirectional"))
    )
    (net (code "204") (name "unconnected-(D14B-I{slash}O-PadF3)") (class "Default")
      (node (ref "D14") (pin "F3") (pinfunction "I/O_F3") (pintype "bidirectional"))
    )
    (net (code "205") (name "unconnected-(D14B-I{slash}O-PadF5)") (class "Default")
      (node (ref "D14") (pin "F5") (pinfunction "I/O_F5") (pintype "bidirectional"))
    )
    (net (code "206") (name "unconnected-(D14B-I{slash}O-PadF12)") (class "Default")
      (node (ref "D14") (pin "F12") (pinfunction "I/O_F12") (pintype "bidirectional"))
    )
    (net (code "207") (name "unconnected-(D14B-I{slash}O-PadF13)") (class "Default")
      (node (ref "D14") (pin "F13") (pinfunction "I/O_F13") (pintype "bidirectional"))
    )
    (net (code "208") (name "unconnected-(D14B-I{slash}O-PadF14)") (class "Default")
      (node (ref "D14") (pin "F14") (pinfunction "I/O_F14") (pintype "bidirectional"))
    )
    (net (code "209") (name "unconnected-(D14B-I{slash}O-PadG3)") (class "Default")
      (node (ref "D14") (pin "G3") (pinfunction "I/O_G3") (pintype "bidirectional"))
    )
    (net (code "210") (name "unconnected-(D14B-I{slash}O-PadG4)") (class "Default")
      (node (ref "D14") (pin "G4") (pinfunction "I/O_G4") (pintype "bidirectional"))
    )
    (net (code "211") (name "unconnected-(D14B-I{slash}O-PadG5)") (class "Default")
      (node (ref "D14") (pin "G5") (pinfunction "I/O_G5") (pintype "bidirectional"))
    )
    (net (code "212") (name "unconnected-(D14B-I{slash}O-PadG11)") (class "Default")
      (node (ref "D14") (pin "G11") (pinfunction "I/O_G11") (pintype "bidirectional"))
    )
    (net (code "213") (name "unconnected-(D14B-I{slash}O-PadG13)") (class "Default")
      (node (ref "D14") (pin "G13") (pinfunction "I/O_G13") (pintype "bidirectional"))
    )
    (net (code "214") (name "unconnected-(D14B-I{slash}O-PadG14)") (class "Default")
      (node (ref "D14") (pin "G14") (pinfunction "I/O_G14") (pintype "bidirectional"))
    )
    (net (code "215") (name "unconnected-(D14B-I{slash}O-PadH1)") (class "Default")
      (node (ref "D14") (pin "H1") (pinfunction "I/O_H1") (pintype "bidirectional"))
    )
    (net (code "216") (name "unconnected-(D14B-I{slash}O-PadH2)") (class "Default")
      (node (ref "D14") (pin "H2") (pinfunction "I/O_H2") (pintype "bidirectional"))
    )
    (net (code "217") (name "unconnected-(D14B-I{slash}O-PadH3)") (class "Default")
      (node (ref "D14") (pin "H3") (pinfunction "I/O_H3") (pintype "bidirectional"))
    )
    (net (code "218") (name "unconnected-(D14B-I{slash}O-PadH4)") (class "Default")
      (node (ref "D14") (pin "H4") (pinfunction "I/O_H4") (pintype "bidirectional"))
    )
    (net (code "219") (name "unconnected-(D14B-I{slash}O-PadH5)") (class "Default")
      (node (ref "D14") (pin "H5") (pinfunction "I/O_H5") (pintype "bidirectional"))
    )
    (net (code "220") (name "unconnected-(D14B-I{slash}O-PadH12)") (class "Default")
      (node (ref "D14") (pin "H12") (pinfunction "I/O_H12") (pintype "bidirectional"))
    )
    (net (code "221") (name "unconnected-(D14B-I{slash}O-PadH13)") (class "Default")
      (node (ref "D14") (pin "H13") (pinfunction "I/O_H13") (pintype "bidirectional"))
    )
    (net (code "222") (name "unconnected-(D14B-I{slash}O-PadH14)") (class "Default")
      (node (ref "D14") (pin "H14") (pinfunction "I/O_H14") (pintype "bidirectional"))
    )
    (net (code "223") (name "unconnected-(D14B-I{slash}O-PadH15)") (class "Default")
      (node (ref "D14") (pin "H15") (pinfunction "I/O_H15") (pintype "bidirectional"))
    )
    (net (code "224") (name "unconnected-(D14B-I{slash}O-PadH16)") (class "Default")
      (node (ref "D14") (pin "H16") (pinfunction "I/O_H16") (pintype "bidirectional"))
    )
    (net (code "225") (name "unconnected-(D14B-I{slash}O-PadJ12)") (class "Default")
      (node (ref "D14") (pin "J12") (pinfunction "I/O_J12") (pintype "bidirectional"))
    )
    (net (code "226") (name "unconnected-(D14F-NC-PadA1)") (class "Default")
      (node (ref "D14") (pin "A1") (pinfunction "NC_A1") (pintype "passive+no_connect"))
    )
    (net (code "227") (name "unconnected-(D14F-NC-PadC2)") (class "Default")
      (node (ref "D14") (pin "C2") (pinfunction "NC_C2") (pintype "passive+no_connect"))
    )
    (net (code "228") (name "unconnected-(D14F-NC-PadC5)") (class "Default")
      (node (ref "D14") (pin "C5") (pinfunction "NC_C5") (pintype "passive+no_connect"))
    )
    (net (code "229") (name "unconnected-(D14F-NC-PadC6)") (class "Default")
      (node (ref "D14") (pin "C6") (pinfunction "NC_C6") (pintype "passive+no_connect"))
    )
    (net (code "230") (name "unconnected-(D14F-NC-PadC15)") (class "Default")
      (node (ref "D14") (pin "C15") (pinfunction "NC_C15") (pintype "passive+no_connect"))
    )
    (net (code "231") (name "unconnected-(D14F-NC-PadD1)") (class "Default")
      (node (ref "D14") (pin "D1") (pinfunction "NC_D1") (pintype "passive+no_connect"))
    )
    (net (code "232") (name "unconnected-(D14F-NC-PadD6)") (class "Default")
      (node (ref "D14") (pin "D6") (pinfunction "NC_D6") (pintype "passive+no_connect"))
    )
    (net (code "233") (name "unconnected-(D14F-NC-PadD14)") (class "Default")
      (node (ref "D14") (pin "D14") (pinfunction "NC_D14") (pintype "passive+no_connect"))
    )
    (net (code "234") (name "unconnected-(D14F-NC-PadD16)") (class "Default")
      (node (ref "D14") (pin "D16") (pinfunction "NC_D16") (pintype "passive+no_connect"))
    )
    (net (code "235") (name "unconnected-(D14F-NC-PadE1)") (class "Default")
      (node (ref "D14") (pin "E1") (pinfunction "NC_E1") (pintype "passive+no_connect"))
    )
    (net (code "236") (name "unconnected-(D14F-NC-PadE6)") (class "Default")
      (node (ref "D14") (pin "E6") (pinfunction "NC_E6") (pintype "passive+no_connect"))
    )
    (net (code "237") (name "unconnected-(D14F-NC-PadE7)") (class "Default")
      (node (ref "D14") (pin "E7") (pinfunction "NC_E7") (pintype "passive+no_connect"))
    )
    (net (code "238") (name "unconnected-(D14F-NC-PadF1)") (class "Default")
      (node (ref "D14") (pin "F1") (pinfunction "NC_F1") (pintype "passive+no_connect"))
    )
    (net (code "239") (name "unconnected-(D14F-NC-PadG1)") (class "Default")
      (node (ref "D14") (pin "G1") (pinfunction "NC_G1") (pintype "passive+no_connect"))
    )
    (net (code "240") (name "unconnected-(D14F-NC-PadG2)") (class "Default")
      (node (ref "D14") (pin "G2") (pinfunction "NC_G2") (pintype "passive+no_connect"))
    )
    (net (code "241") (name "unconnected-(D14F-NC-PadG12)") (class "Default")
      (node (ref "D14") (pin "G12") (pinfunction "NC_G12") (pintype "passive+no_connect"))
    )
    (net (code "242") (name "unconnected-(D14F-NC-PadJ16)") (class "Default")
      (node (ref "D14") (pin "J16") (pinfunction "NC_J16") (pintype "passive+no_connect"))
    )
    (net (code "243") (name "unconnected-(D14F-NC-PadK12)") (class "Default")
      (node (ref "D14") (pin "K12") (pinfunction "NC_K12") (pintype "passive+no_connect"))
    )
    (net (code "244") (name "unconnected-(D14F-NC-PadM4)") (class "Default")
      (node (ref "D14") (pin "M4") (pinfunction "NC_M4") (pintype "passive+no_connect"))
    )
    (net (code "245") (name "unconnected-(D14F-NC-PadM9)") (class "Default")
      (node (ref "D14") (pin "M9") (pinfunction "NC_M9") (pintype "passive+no_connect"))
    )
    (net (code "246") (name "unconnected-(D14F-NC-PadM10)") (class "Default")
      (node (ref "D14") (pin "M10") (pinfunction "NC_M10") (pintype "passive+no_connect"))
    )
    (net (code "247") (name "unconnected-(D14F-NC-PadP9)") (class "Default")
      (node (ref "D14") (pin "P9") (pinfunction "NC_P9") (pintype "passive+no_connect"))
    )
    (net (code "248") (name "unconnected-(D14F-NC-PadP11)") (class "Default")
      (node (ref "D14") (pin "P11") (pinfunction "NC_P11") (pintype "passive+no_connect"))
    )
    (net (code "249") (name "unconnected-(D14F-NC-PadT9)") (class "Default")
      (node (ref "D14") (pin "T9") (pinfunction "NC_T9") (pintype "passive+no_connect"))
    )
    (net (code "250") (name "unconnected-(D14F-NC-PadT11)") (class "Default")
      (node (ref "D14") (pin "T11") (pinfunction "NC_T11") (pintype "passive+no_connect"))
    )
    (net (code "251") (name "unconnected-(D14F-NC-PadT12)") (class "Default")
      (node (ref "D14") (pin "T12") (pinfunction "NC_T12") (pintype "passive+no_connect"))
    )
    (net (code "252") (name "unconnected-(D14F-NC-PadT13)") (class "Default")
      (node (ref "D14") (pin "T13") (pinfunction "NC_T13") (pintype "passive+no_connect"))
    )
    (net (code "253") (name "unconnected-(D14F-NC-PadT14)") (class "Default")
      (node (ref "D14") (pin "T14") (pinfunction "NC_T14") (pintype "passive+no_connect"))
    )
    (net (code "254") (name "unconnected-(R36-Pad1)") (class "Default")
      (node (ref "R36") (pin "1") (pinfunction "1_1") (pintype "passive"))
    )
    (net (code "255") (name "unconnected-(R36-Pad8)") (class "Default")
      (node (ref "R36") (pin "8") (pinfunction "8_8") (pintype "passive"))
    )
    (net (code "256") (name "unconnected-(R37-Pad4)") (class "Default")
      (node (ref "R37") (pin "4") (pinfunction "4_4") (pintype "passive"))
    )
    (net (code "257") (name "unconnected-(R37-Pad5)") (class "Default")
      (node (ref "R37") (pin "5") (pinfunction "5_5") (pintype "passive"))
    )
    (net (code "258") (name "unconnected-(X3-Pad12)") (class "Default")
      (node (ref "X3") (pin "12") (pinfunction "12_12") (pintype "passive+no_connect"))
    )
    (net (code "259") (name "unconnected-(X3-Pad14)") (class "Default")
      (node (ref "X3") (pin "14") (pinfunction "14_14") (pintype "passive+no_connect"))
    )
  )
)
